# PDMC-S04-V00-TempSensor.net
KiCad netlist of a schematic drawn in Altium Designer
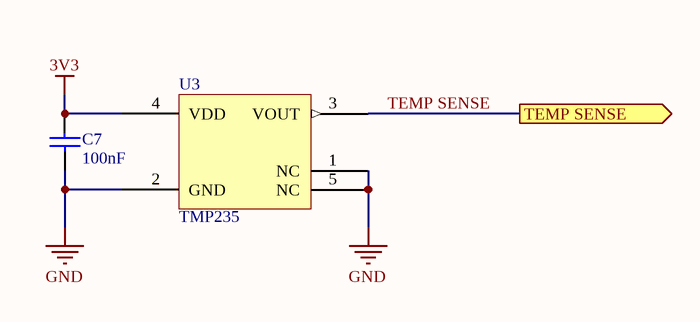
[diagram p0: PDMC-S04-V00-TempSensor.SchDoc]

(export (version "E")
  (design (tool "Eeschema 10.0.6"))
  (components
    (comp (ref "C7")
      (value "100nF")
      (footprint "Cap_Ceramic_0603")
      (description "Capacitor, Ceramic, SMD, 100nF, 50V, 5%, X7R, 0603")
      (libsource (lib "StandardCapacitors") (part "100nF 50V 5% X7R 0603"))
    )
    (comp (ref "U3")
      (value "TMP235")
      (footprint "SC70")
      (description "TMP235, Low-Power, High-Accuracy Analog Output Temperature Sensor")
      (libsource (lib "PDM-CARD-SCHLib-V00") (part "TMP235"))
    )
  )
  (nets
    (net (code "1") (name "/TEMP SENSE") (class "Default")
      (node (ref "U3") (pin "3") (pinfunction "VOUT_3") (pintype "output"))
    )
    (net (code "2") (name "3V3") (class "Default")
      (node (ref "C7") (pin "2") (pinfunction "2_2") (pintype "passive"))
      (node (ref "U3") (pin "4") (pinfunction "VDD_4") (pintype "passive"))
    )
    (net (code "3") (name "GND") (class "Default")
      (node (ref "C7") (pin "1") (pinfunction "1_1") (pintype "passive"))
      (node (ref "U3") (pin "1") (pinfunction "NC_1") (pintype "passive"))
      (node (ref "U3") (pin "2") (pinfunction "GND_2") (pintype "passive"))
      (node (ref "U3") (pin "5") (pinfunction "NC_5") (pintype "passive"))
    )
  )
)
